# simreader_v10.net
KiCad netlist of a schematic drawn in EAGLE
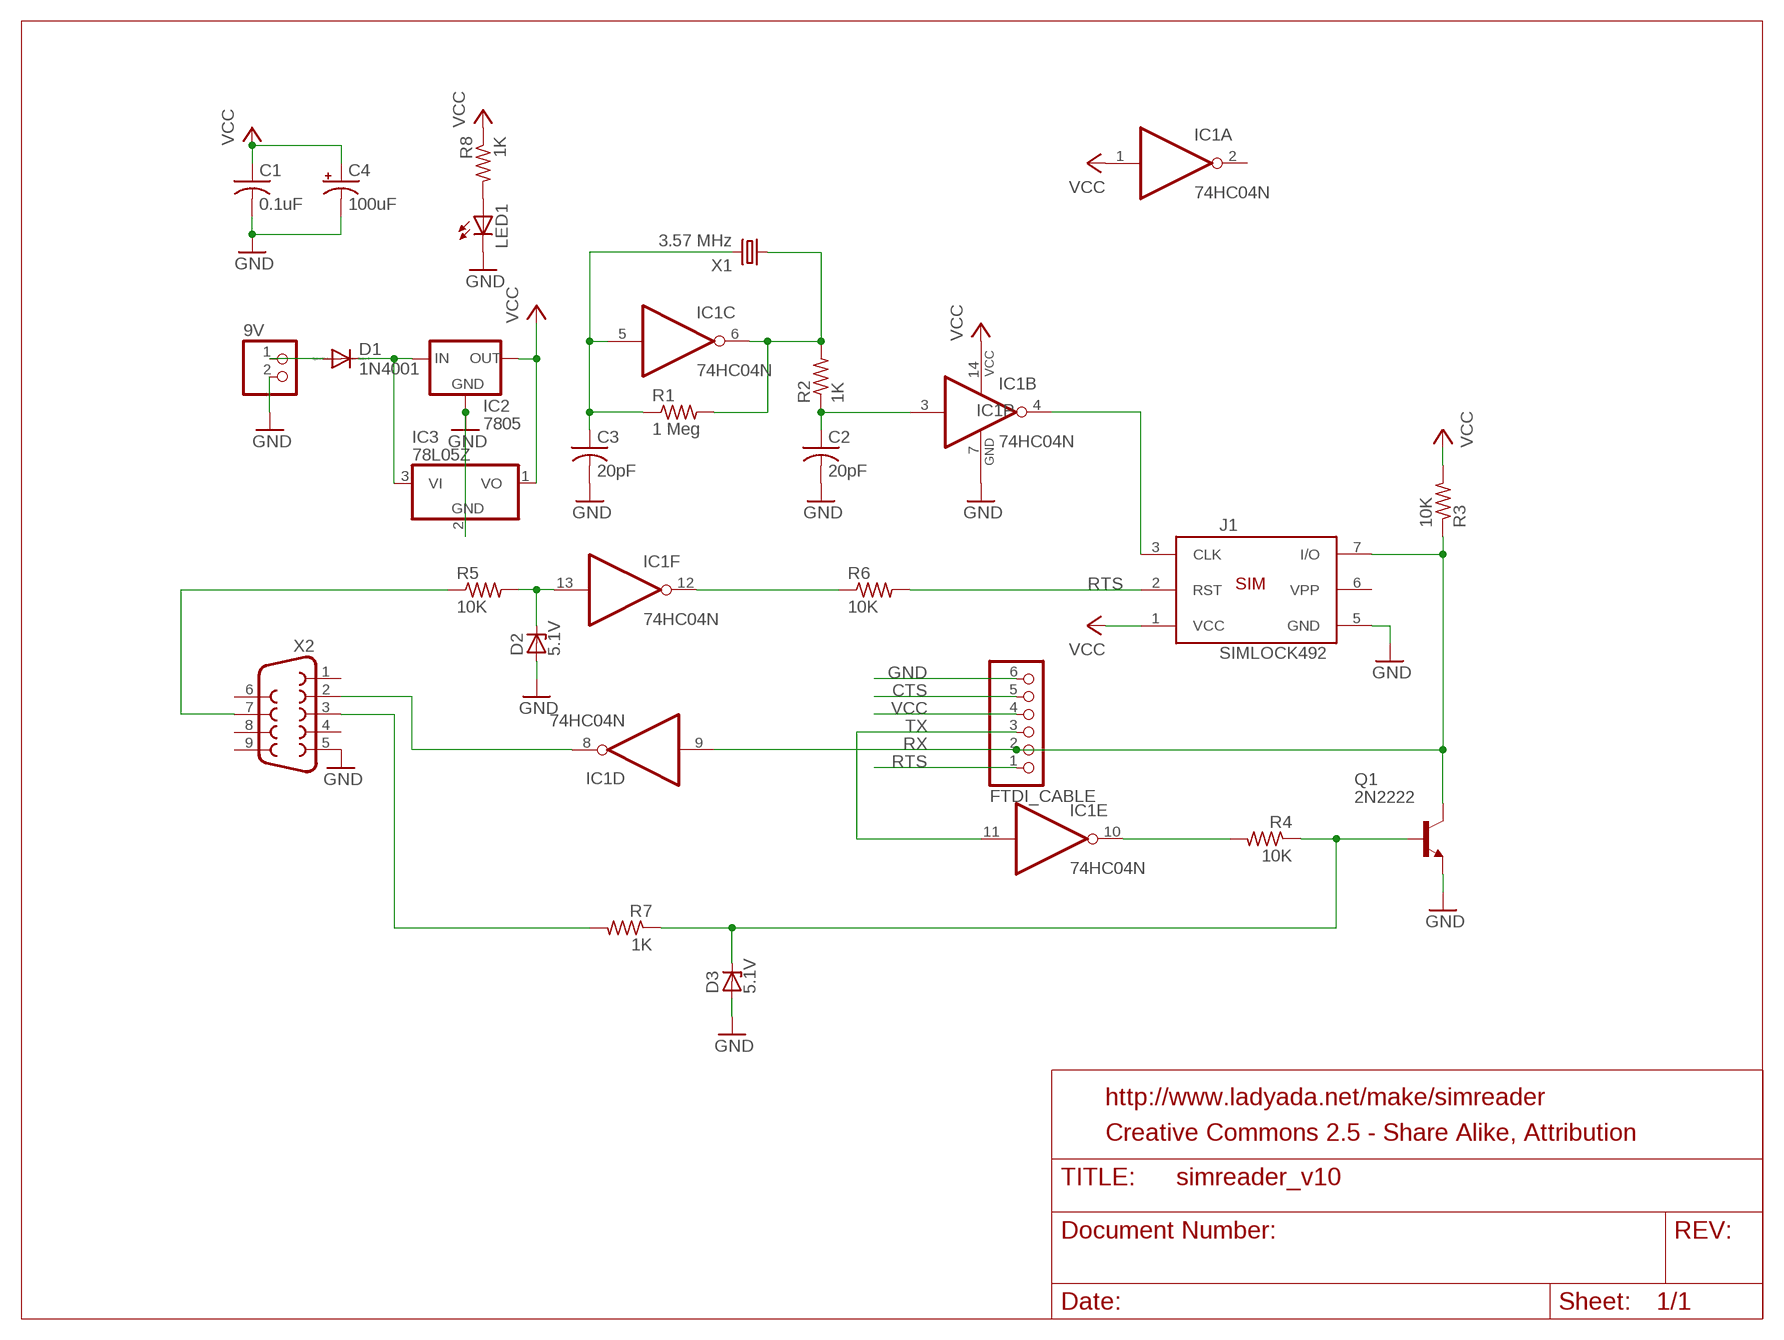
[diagram p0: schematic, sheet 1]

(export (version "E")
  (design (tool "Eeschema 10.0.6"))
  (components
    (comp (ref "9V")
      (value "PINHD-1X2")
      (footprint "eagle-import:1X02")
      (libsource (lib "eagle-import") (part "PINHD-1X2"))
    )
    (comp (ref "C1")
      (value "0.1uF")
      (footprint "eagle-import:C025-025X050")
      (libsource (lib "eagle-import") (part "C-US025-025X050"))
    )
    (comp (ref "C2")
      (value "20pF")
      (footprint "eagle-import:C025-025X050")
      (libsource (lib "eagle-import") (part "C-US025-025X050"))
    )
    (comp (ref "C3")
      (value "20pF")
      (footprint "eagle-import:C025-025X050")
      (libsource (lib "eagle-import") (part "C-US025-025X050"))
    )
    (comp (ref "C4")
      (value "100uF")
      (footprint "eagle-import:E2,5-5")
      (libsource (lib "eagle-import") (part "CPOL-USE2.5-5"))
    )
    (comp (ref "D1")
      (value "1N4001")
      (footprint "eagle-import:DO41-10")
      (libsource (lib "eagle-import") (part "1N4004"))
    )
    (comp (ref "D2")
      (value "5.1V")
      (footprint "eagle-import:DO35Z10")
      (libsource (lib "eagle-import") (part "ZENER-DIODEDO35Z10"))
    )
    (comp (ref "D3")
      (value "5.1V")
      (footprint "eagle-import:DO35Z10")
      (libsource (lib "eagle-import") (part "ZENER-DIODEDO35Z10"))
    )
    (comp (ref "FTDI_CABLE")
      (value "PINHD-1X6")
      (footprint "eagle-import:1X06")
      (libsource (lib "eagle-import") (part "PINHD-1X6"))
    )
    (comp (ref "IC1")
      (value "74HC04N")
      (footprint "eagle-import:DIL14")
      (libsource (lib "eagle-import") (part "7404NLS"))
    )
    (comp (ref "IC2")
      (value "7805")
      (footprint "eagle-import:78XXS")
      (libsource (lib "eagle-import") (part "78XXS"))
    )
    (comp (ref "IC3")
      (value "78L05Z")
      (footprint "eagle-import:TO92")
      (libsource (lib "eagle-import") (part "78ZL05"))
    )
    (comp (ref "J1")
      (value "SIMLOCK492")
      (footprint "eagle-import:5002")
      (libsource (lib "eagle-import") (part "SIMLOCK492"))
    )
    (comp (ref "LED1")
      (value "LED3MM")
      (footprint "eagle-import:LED3MM")
      (libsource (lib "eagle-import") (part "LED3MM"))
    )
    (comp (ref "Q1")
      (value "2N2222")
      (footprint "eagle-import:TO92-EBC")
      (libsource (lib "eagle-import") (part "2N2222"))
    )
    (comp (ref "R1")
      (value "1 Meg")
      (footprint "eagle-import:0207_10")
      (libsource (lib "eagle-import") (part "R-US_0207/10"))
    )
    (comp (ref "R2")
      (value "1K")
      (footprint "eagle-import:0207_10")
      (libsource (lib "eagle-import") (part "R-US_0207/10"))
    )
    (comp (ref "R3")
      (value "10K")
      (footprint "eagle-import:0207_10")
      (libsource (lib "eagle-import") (part "R-US_0207/10"))
    )
    (comp (ref "R4")
      (value "10K")
      (footprint "eagle-import:0207_10")
      (libsource (lib "eagle-import") (part "R-US_0207/10"))
    )
    (comp (ref "R5")
      (value "10K")
      (footprint "eagle-import:0207_10")
      (libsource (lib "eagle-import") (part "R-US_0207/10"))
    )
    (comp (ref "R6")
      (value "10K")
      (footprint "eagle-import:0207_10")
      (libsource (lib "eagle-import") (part "R-US_0207/10"))
    )
    (comp (ref "R7")
      (value "1K")
      (footprint "eagle-import:0207_10")
      (libsource (lib "eagle-import") (part "R-US_0207/10"))
    )
    (comp (ref "R8")
      (value "1K")
      (footprint "eagle-import:0207_10")
      (libsource (lib "eagle-import") (part "R-US_0207/10"))
    )
    (comp (ref "X1")
      (value "3.57 MHz")
      (footprint "eagle-import:HC49")
      (libsource (lib "eagle-import") (part "CRYSTAL"))
    )
    (comp (ref "X2")
      (value "F09D")
      (footprint "eagle-import:F09D")
      (libsource (lib "eagle-import") (part "F09D"))
    )
  )
  (nets
    (net (code "1") (name "/CTS") (class "Default")
      (node (ref "FTDI_CABLE") (pin "5") (pinfunction "5_5") (pintype "passive"))
    )
    (net (code "2") (name "/RTS") (class "Default")
      (node (ref "FTDI_CABLE") (pin "1") (pinfunction "1_1") (pintype "passive"))
      (node (ref "J1") (pin "2") (pinfunction "RST_2") (pintype "bidirectional"))
      (node (ref "R6") (pin "2") (pinfunction "2_2") (pintype "passive"))
    )
    (net (code "3") (name "/RX") (class "Default")
      (node (ref "FTDI_CABLE") (pin "2") (pinfunction "2_2") (pintype "passive"))
      (node (ref "IC1") (pin "9") (pinfunction "I_9") (pintype "input"))
      (node (ref "J1") (pin "7") (pinfunction "I/O_7") (pintype "bidirectional"))
      (node (ref "Q1") (pin "C") (pinfunction "C_C") (pintype "passive"))
      (node (ref "R3") (pin "1") (pinfunction "1_1") (pintype "passive"))
    )
    (net (code "4") (name "/TX") (class "Default")
      (node (ref "FTDI_CABLE") (pin "3") (pinfunction "3_3") (pintype "passive"))
      (node (ref "IC1") (pin "11") (pinfunction "I_11") (pintype "input"))
    )
    (net (code "5") (name "GND") (class "Default")
      (node (ref "9V") (pin "2") (pinfunction "2_2") (pintype "passive"))
      (node (ref "C1") (pin "2") (pinfunction "2_2") (pintype "passive"))
      (node (ref "C2") (pin "2") (pinfunction "2_2") (pintype "passive"))
      (node (ref "C3") (pin "2") (pinfunction "2_2") (pintype "passive"))
      (node (ref "C4") (pin "-") (pinfunction "-_-") (pintype "passive"))
      (node (ref "D2") (pin "A") (pinfunction "A_A") (pintype "passive"))
      (node (ref "D3") (pin "A") (pinfunction "A_A") (pintype "passive"))
      (node (ref "FTDI_CABLE") (pin "6") (pinfunction "6_6") (pintype "passive"))
      (node (ref "IC1") (pin "7") (pinfunction "GND_7") (pintype "power_in"))
      (node (ref "IC2") (pin "GND") (pinfunction "GND_GND") (pintype "input"))
      (node (ref "IC3") (pin "2") (pinfunction "GND_2") (pintype "passive"))
      (node (ref "J1") (pin "5") (pinfunction "GND_5") (pintype "bidirectional"))
      (node (ref "LED1") (pin "K") (pinfunction "C_K") (pintype "passive"))
      (node (ref "Q1") (pin "E") (pinfunction "E_E") (pintype "passive"))
      (node (ref "X2") (pin "5") (pinfunction "5_5") (pintype "passive"))
    )
    (net (code "6") (name "Net-(9V-Pad1)") (class "Default")
      (node (ref "9V") (pin "1") (pinfunction "1_1") (pintype "passive"))
      (node (ref "D1") (pin "A") (pinfunction "A_A") (pintype "passive"))
    )
    (net (code "7") (name "Net-(D3-PadC)") (class "Default")
      (node (ref "D3") (pin "C") (pinfunction "C_C") (pintype "passive"))
      (node (ref "Q1") (pin "B") (pinfunction "B_B") (pintype "passive"))
      (node (ref "R4") (pin "1") (pinfunction "1_1") (pintype "passive"))
      (node (ref "R7") (pin "1") (pinfunction "1_1") (pintype "passive"))
    )
    (net (code "8") (name "Net-(IC1B-I)") (class "Default")
      (node (ref "C2") (pin "1") (pinfunction "1_1") (pintype "passive"))
      (node (ref "IC1") (pin "3") (pinfunction "I_3") (pintype "input"))
      (node (ref "R2") (pin "1") (pinfunction "1_1") (pintype "passive"))
    )
    (net (code "9") (name "Net-(IC1B-O)") (class "Default")
      (node (ref "IC1") (pin "4") (pinfunction "O_4") (pintype "output"))
      (node (ref "J1") (pin "3") (pinfunction "CLK_3") (pintype "bidirectional"))
    )
    (net (code "10") (name "Net-(IC1C-I)") (class "Default")
      (node (ref "C3") (pin "1") (pinfunction "1_1") (pintype "passive"))
      (node (ref "IC1") (pin "5") (pinfunction "I_5") (pintype "input"))
      (node (ref "R1") (pin "1") (pinfunction "1_1") (pintype "passive"))
      (node (ref "X1") (pin "2") (pinfunction "2_2") (pintype "passive"))
    )
    (net (code "11") (name "Net-(IC1C-O)") (class "Default")
      (node (ref "IC1") (pin "6") (pinfunction "O_6") (pintype "output"))
      (node (ref "R1") (pin "2") (pinfunction "2_2") (pintype "passive"))
      (node (ref "R2") (pin "2") (pinfunction "2_2") (pintype "passive"))
      (node (ref "X1") (pin "1") (pinfunction "1_1") (pintype "passive"))
    )
    (net (code "12") (name "Net-(IC1D-O)") (class "Default")
      (node (ref "IC1") (pin "8") (pinfunction "O_8") (pintype "output"))
      (node (ref "X2") (pin "2") (pinfunction "2_2") (pintype "passive"))
    )
    (net (code "13") (name "Net-(IC1E-O)") (class "Default")
      (node (ref "IC1") (pin "10") (pinfunction "O_10") (pintype "output"))
      (node (ref "R4") (pin "2") (pinfunction "2_2") (pintype "passive"))
    )
    (net (code "14") (name "Net-(IC1F-I)") (class "Default")
      (node (ref "D2") (pin "C") (pinfunction "C_C") (pintype "passive"))
      (node (ref "IC1") (pin "13") (pinfunction "I_13") (pintype "input"))
      (node (ref "R5") (pin "2") (pinfunction "2_2") (pintype "passive"))
    )
    (net (code "15") (name "Net-(IC1F-O)") (class "Default")
      (node (ref "IC1") (pin "12") (pinfunction "O_12") (pintype "output"))
      (node (ref "R6") (pin "1") (pinfunction "1_1") (pintype "passive"))
    )
    (net (code "16") (name "Net-(IC3-VI)") (class "Default")
      (node (ref "D1") (pin "C") (pinfunction "C_C") (pintype "passive"))
      (node (ref "IC2") (pin "IN") (pinfunction "IN_IN") (pintype "input"))
      (node (ref "IC3") (pin "3") (pinfunction "VI_3") (pintype "input"))
    )
    (net (code "17") (name "Net-(LED1-PadA)") (class "Default")
      (node (ref "LED1") (pin "A") (pinfunction "A_A") (pintype "passive"))
      (node (ref "R8") (pin "2") (pinfunction "2_2") (pintype "passive"))
    )
    (net (code "18") (name "Net-(R5-Pad1)") (class "Default")
      (node (ref "R5") (pin "1") (pinfunction "1_1") (pintype "passive"))
      (node (ref "X2") (pin "7") (pinfunction "7_7") (pintype "passive"))
    )
    (net (code "19") (name "Net-(R7-Pad2)") (class "Default")
      (node (ref "R7") (pin "2") (pinfunction "2_2") (pintype "passive"))
      (node (ref "X2") (pin "3") (pinfunction "3_3") (pintype "passive"))
    )
    (net (code "20") (name "VCC") (class "Default")
      (node (ref "C1") (pin "1") (pinfunction "1_1") (pintype "passive"))
      (node (ref "C4") (pin "+") (pinfunction "+_+") (pintype "passive"))
      (node (ref "FTDI_CABLE") (pin "4") (pinfunction "4_4") (pintype "passive"))
      (node (ref "IC1") (pin "1") (pinfunction "I_1") (pintype "input"))
      (node (ref "IC1") (pin "14") (pinfunction "VCC_14") (pintype "power_in"))
      (node (ref "IC2") (pin "OUT") (pinfunction "OUT_OUT") (pintype "passive"))
      (node (ref "IC3") (pin "1") (pinfunction "VO_1") (pintype "passive"))
      (node (ref "J1") (pin "1") (pinfunction "VCC_1") (pintype "bidirectional"))
      (node (ref "R3") (pin "2") (pinfunction "2_2") (pintype "passive"))
      (node (ref "R8") (pin "1") (pinfunction "1_1") (pintype "passive"))
    )
    (net (code "21") (name "unconnected-(IC1A-O-Pad2)") (class "Default")
      (node (ref "IC1") (pin "2") (pinfunction "O_2") (pintype "output"))
    )
    (net (code "22") (name "unconnected-(J1-VPP-Pad6)") (class "Default")
      (node (ref "J1") (pin "6") (pinfunction "VPP_6") (pintype "bidirectional"))
    )
    (net (code "23") (name "unconnected-(X2-Pad1)") (class "Default")
      (node (ref "X2") (pin "1") (pinfunction "1_1") (pintype "passive"))
    )
    (net (code "24") (name "unconnected-(X2-Pad4)") (class "Default")
      (node (ref "X2") (pin "4") (pinfunction "4_4") (pintype "passive"))
    )
    (net (code "25") (name "unconnected-(X2-Pad6)") (class "Default")
      (node (ref "X2") (pin "6") (pinfunction "6_6") (pintype "passive"))
    )
    (net (code "26") (name "unconnected-(X2-Pad8)") (class "Default")
      (node (ref "X2") (pin "8") (pinfunction "8_8") (pintype "passive"))
    )
    (net (code "27") (name "unconnected-(X2-Pad9)") (class "Default")
      (node (ref "X2") (pin "9") (pinfunction "9_9") (pintype "passive"))
    )
  )
)
